# Simple_Lux_Logger.net
KiCad netlist of a schematic drawn in EAGLE
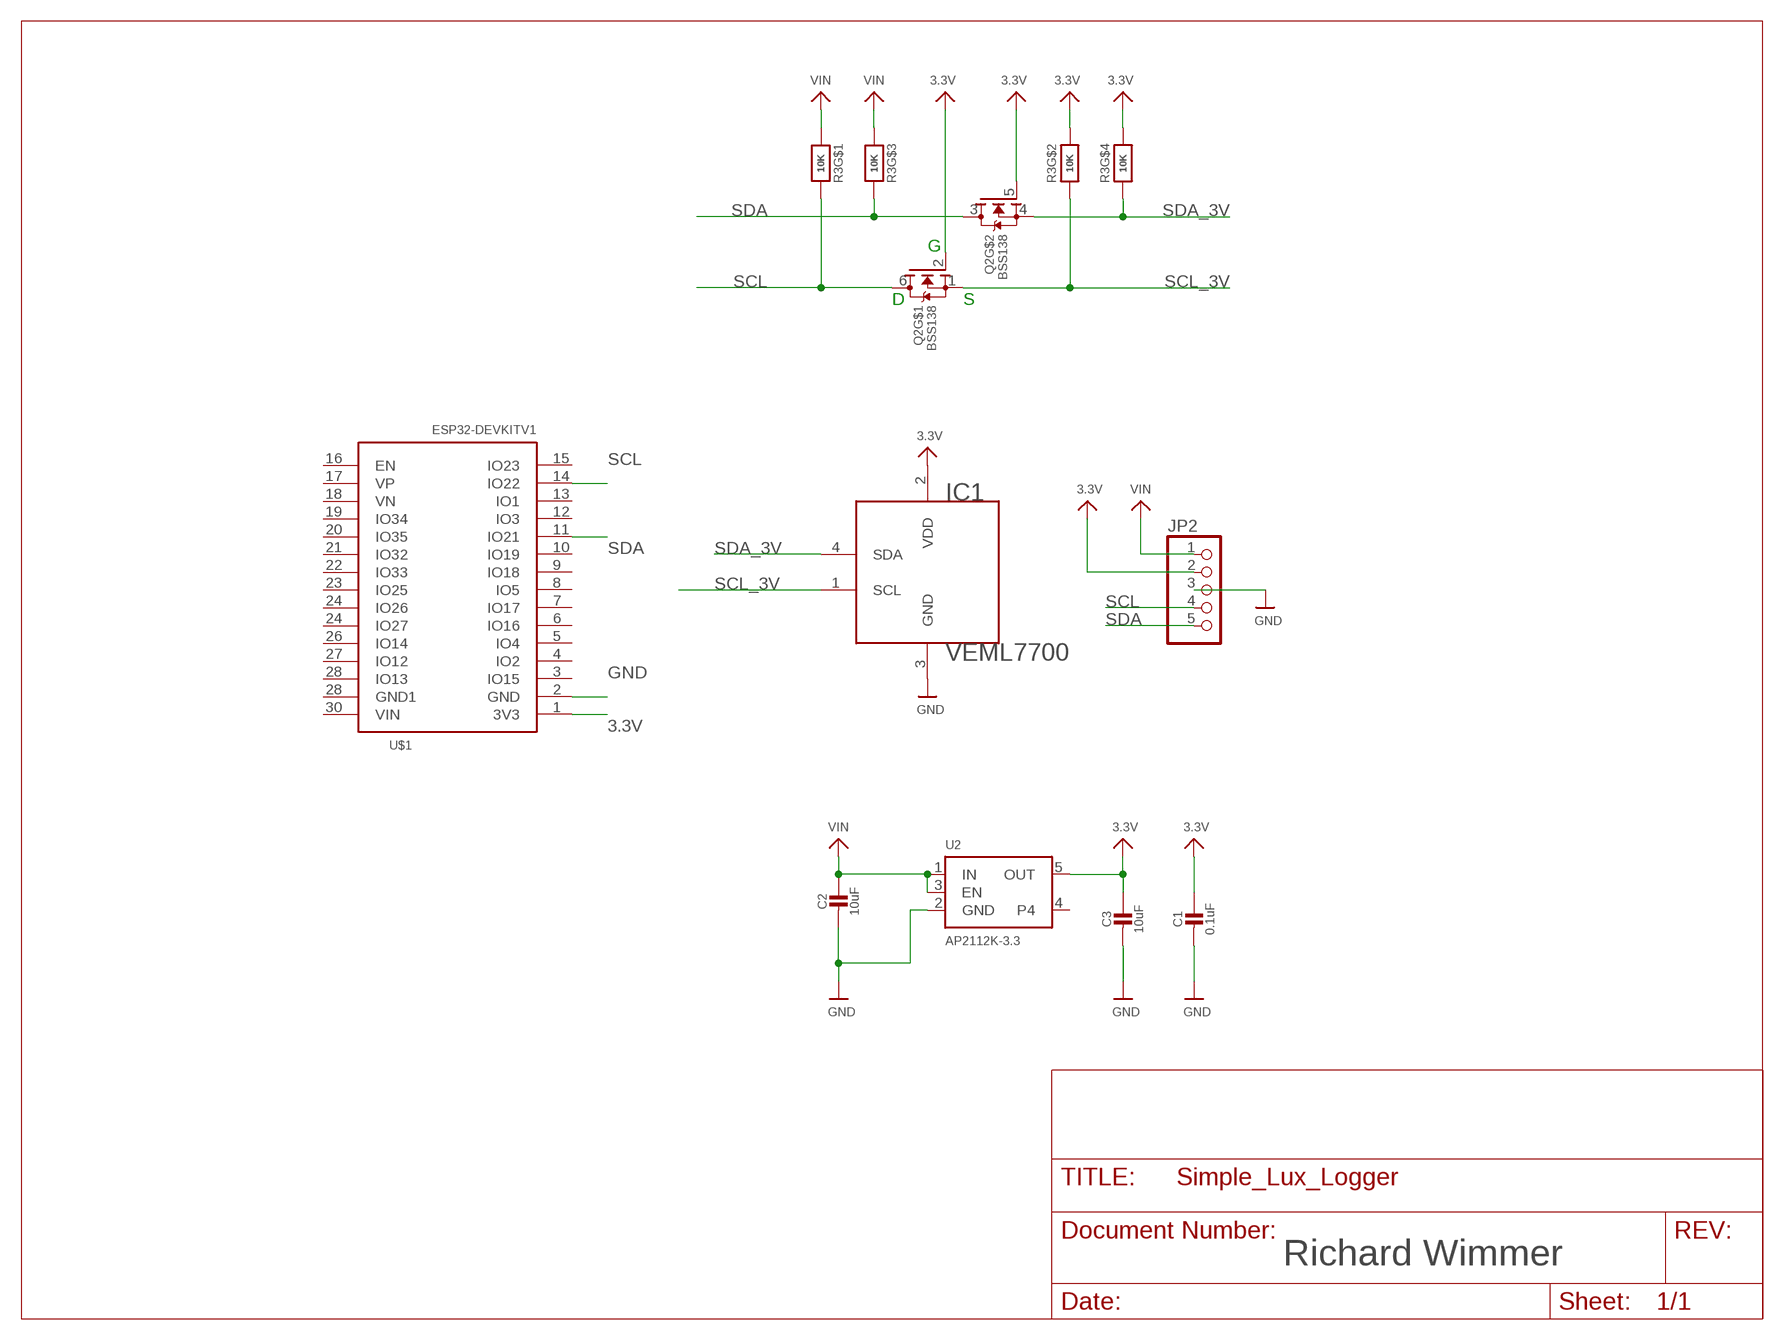
[diagram p0: schematic, sheet 1]

(export (version "E")
  (design (tool "Eeschema 10.0.6"))
  (components
    (comp (ref "C1")
      (value "0.1uF")
      (footprint "eagle-import:0603-NO")
      (libsource (lib "eagle-import") (part "CAP_CERAMIC0603_NO"))
    )
    (comp (ref "C2")
      (value "10uF")
      (footprint "eagle-import:0805-NO")
      (libsource (lib "eagle-import") (part "CAP_CERAMIC0805-NOOUTLINE"))
    )
    (comp (ref "C3")
      (value "10uF")
      (footprint "eagle-import:0805-NO")
      (libsource (lib "eagle-import") (part "CAP_CERAMIC0805-NOOUTLINE"))
    )
    (comp (ref "IC1")
      (value "VEML7700")
      (footprint "eagle-import:VEML7700")
      (libsource (lib "eagle-import") (part "VEML7700"))
    )
    (comp (ref "JP2")
      (value "HEADER-1X5ROUND")
      (footprint "eagle-import:1X05_ROUND")
      (libsource (lib "eagle-import") (part "HEADER-1X5ROUND"))
    )
    (comp (ref "Q2")
      (value "BSS138")
      (footprint "eagle-import:SOT363")
      (libsource (lib "eagle-import") (part "MOSFET-N_DUAL"))
    )
    (comp (ref "R3")
      (value "10K")
      (footprint "eagle-import:RESPACK_4X0603")
      (libsource (lib "eagle-import") (part "RESISTOR_4PACK"))
    )
    (comp (ref "U$1")
      (value "ESP32DEVKITV1")
      (footprint "eagle-import:ESP32-DEVKITV1")
      (libsource (lib "eagle-import") (part "ESP32DEVKITV1"))
    )
    (comp (ref "U2")
      (value "AP2112K-3.3")
      (footprint "eagle-import:SOT23-5")
      (libsource (lib "eagle-import") (part "VREG_SOT23-5"))
    )
  )
  (nets
    (net (code "1") (name "/SCL") (class "Default")
      (node (ref "JP2") (pin "4") (pinfunction "4_4") (pintype "passive"))
      (node (ref "Q2") (pin "6") (pinfunction "D_6") (pintype "bidirectional"))
      (node (ref "R3") (pin "8") (pinfunction "2_8") (pintype "passive"))
      (node (ref "U$1") (pin "14") (pinfunction "IO22_14") (pintype "bidirectional"))
    )
    (net (code "2") (name "/SCL_3V") (class "Default")
      (node (ref "IC1") (pin "1") (pinfunction "SCL_1") (pintype "bidirectional"))
      (node (ref "Q2") (pin "1") (pinfunction "S_1") (pintype "bidirectional"))
      (node (ref "R3") (pin "7") (pinfunction "2_7") (pintype "passive"))
    )
    (net (code "3") (name "/SDA") (class "Default")
      (node (ref "JP2") (pin "5") (pinfunction "5_5") (pintype "passive"))
      (node (ref "Q2") (pin "3") (pinfunction "D_3") (pintype "bidirectional"))
      (node (ref "R3") (pin "6") (pinfunction "2_6") (pintype "passive"))
      (node (ref "U$1") (pin "11") (pinfunction "IO21_11") (pintype "bidirectional"))
    )
    (net (code "4") (name "/SDA_3V") (class "Default")
      (node (ref "IC1") (pin "4") (pinfunction "SDA_4") (pintype "bidirectional"))
      (node (ref "Q2") (pin "4") (pinfunction "S_4") (pintype "bidirectional"))
      (node (ref "R3") (pin "5") (pinfunction "2_5") (pintype "passive"))
    )
    (net (code "5") (name "3.3V") (class "Default")
      (node (ref "C1") (pin "1") (pinfunction "1_1") (pintype "passive"))
      (node (ref "C3") (pin "1") (pinfunction "1_1") (pintype "passive"))
      (node (ref "IC1") (pin "2") (pinfunction "VDD_2") (pintype "power_in"))
      (node (ref "JP2") (pin "2") (pinfunction "2_2") (pintype "passive"))
      (node (ref "Q2") (pin "2") (pinfunction "G_2") (pintype "bidirectional"))
      (node (ref "Q2") (pin "5") (pinfunction "G_5") (pintype "bidirectional"))
      (node (ref "R3") (pin "2") (pinfunction "1_2") (pintype "passive"))
      (node (ref "R3") (pin "4") (pinfunction "1_4") (pintype "passive"))
      (node (ref "U$1") (pin "1") (pinfunction "3V3_1") (pintype "bidirectional"))
      (node (ref "U2") (pin "5") (pinfunction "OUT_5") (pintype "power_in"))
    )
    (net (code "6") (name "GND") (class "Default")
      (node (ref "C1") (pin "2") (pinfunction "2_2") (pintype "passive"))
      (node (ref "C2") (pin "2") (pinfunction "2_2") (pintype "passive"))
      (node (ref "C3") (pin "2") (pinfunction "2_2") (pintype "passive"))
      (node (ref "IC1") (pin "3") (pinfunction "GND_3") (pintype "power_in"))
      (node (ref "JP2") (pin "3") (pinfunction "3_3") (pintype "passive"))
      (node (ref "U$1") (pin "2") (pinfunction "GND_2") (pintype "bidirectional"))
      (node (ref "U2") (pin "2") (pinfunction "GND_2") (pintype "power_in"))
    )
    (net (code "7") (name "VIN") (class "Default")
      (node (ref "C2") (pin "1") (pinfunction "1_1") (pintype "passive"))
      (node (ref "JP2") (pin "1") (pinfunction "1_1") (pintype "passive"))
      (node (ref "R3") (pin "1") (pinfunction "1_1") (pintype "passive"))
      (node (ref "R3") (pin "3") (pinfunction "1_3") (pintype "passive"))
      (node (ref "U2") (pin "1") (pinfunction "IN_1") (pintype "power_in"))
      (node (ref "U2") (pin "3") (pinfunction "EN_3") (pintype "input"))
    )
    (net (code "8") (name "unconnected-(U$1-EN-Pad16)") (class "Default")
      (node (ref "U$1") (pin "16") (pinfunction "EN_16") (pintype "bidirectional"))
    )
    (net (code "9") (name "unconnected-(U$1-GND1-Pad28)") (class "Default")
      (node (ref "U$1") (pin "28") (pinfunction "GND1_28") (pintype "bidirectional"))
    )
    (net (code "10") (name "unconnected-(U$1-IO1-Pad13)") (class "Default")
      (node (ref "U$1") (pin "13") (pinfunction "IO1_13") (pintype "bidirectional"))
    )
    (net (code "11") (name "unconnected-(U$1-IO2-Pad4)") (class "Default")
      (node (ref "U$1") (pin "4") (pinfunction "IO2_4") (pintype "bidirectional"))
    )
    (net (code "12") (name "unconnected-(U$1-IO3-Pad12)") (class "Default")
      (node (ref "U$1") (pin "12") (pinfunction "IO3_12") (pintype "bidirectional"))
    )
    (net (code "13") (name "unconnected-(U$1-IO4-Pad5)") (class "Default")
      (node (ref "U$1") (pin "5") (pinfunction "IO4_5") (pintype "bidirectional"))
    )
    (net (code "14") (name "unconnected-(U$1-IO5-Pad8)") (class "Default")
      (node (ref "U$1") (pin "8") (pinfunction "IO5_8") (pintype "bidirectional"))
    )
    (net (code "15") (name "unconnected-(U$1-IO12-Pad27)") (class "Default")
      (node (ref "U$1") (pin "27") (pinfunction "IO12_27") (pintype "bidirectional"))
    )
    (net (code "16") (name "unconnected-(U$1-IO13-Pad28)") (class "Default")
      (node (ref "U$1") (pin "28") (pinfunction "IO13_28") (pintype "bidirectional"))
    )
    (net (code "17") (name "unconnected-(U$1-IO14-Pad26)") (class "Default")
      (node (ref "U$1") (pin "26") (pinfunction "IO14_26") (pintype "bidirectional"))
    )
    (net (code "18") (name "unconnected-(U$1-IO15-Pad3)") (class "Default")
      (node (ref "U$1") (pin "3") (pinfunction "IO15_3") (pintype "bidirectional"))
    )
    (net (code "19") (name "unconnected-(U$1-IO16-Pad6)") (class "Default")
      (node (ref "U$1") (pin "6") (pinfunction "IO16_6") (pintype "bidirectional"))
    )
    (net (code "20") (name "unconnected-(U$1-IO17-Pad7)") (class "Default")
      (node (ref "U$1") (pin "7") (pinfunction "IO17_7") (pintype "bidirectional"))
    )
    (net (code "21") (name "unconnected-(U$1-IO18-Pad9)") (class "Default")
      (node (ref "U$1") (pin "9") (pinfunction "IO18_9") (pintype "bidirectional"))
    )
    (net (code "22") (name "unconnected-(U$1-IO19-Pad10)") (class "Default")
      (node (ref "U$1") (pin "10") (pinfunction "IO19_10") (pintype "bidirectional"))
    )
    (net (code "23") (name "unconnected-(U$1-IO23-Pad15)") (class "Default")
      (node (ref "U$1") (pin "15") (pinfunction "IO23_15") (pintype "bidirectional"))
    )
    (net (code "24") (name "unconnected-(U$1-IO25-Pad23)") (class "Default")
      (node (ref "U$1") (pin "23") (pinfunction "IO25_23") (pintype "bidirectional"))
    )
    (net (code "25") (name "unconnected-(U$1-IO26-Pad24)") (class "Default")
      (node (ref "U$1") (pin "24") (pinfunction "IO26_24") (pintype "bidirectional"))
    )
    (net (code "26") (name "unconnected-(U$1-IO27-Pad24)") (class "Default")
      (node (ref "U$1") (pin "24") (pinfunction "IO27_24") (pintype "bidirectional"))
    )
    (net (code "27") (name "unconnected-(U$1-IO32-Pad21)") (class "Default")
      (node (ref "U$1") (pin "21") (pinfunction "IO32_21") (pintype "bidirectional"))
    )
    (net (code "28") (name "unconnected-(U$1-IO33-Pad22)") (class "Default")
      (node (ref "U$1") (pin "22") (pinfunction "IO33_22") (pintype "bidirectional"))
    )
    (net (code "29") (name "unconnected-(U$1-IO34-Pad19)") (class "Default")
      (node (ref "U$1") (pin "19") (pinfunction "IO34_19") (pintype "bidirectional"))
    )
    (net (code "30") (name "unconnected-(U$1-IO35-Pad20)") (class "Default")
      (node (ref "U$1") (pin "20") (pinfunction "IO35_20") (pintype "bidirectional"))
    )
    (net (code "31") (name "unconnected-(U$1-VIN-Pad30)") (class "Default")
      (node (ref "U$1") (pin "30") (pinfunction "VIN_30") (pintype "bidirectional"))
    )
    (net (code "32") (name "unconnected-(U$1-VN-Pad18)") (class "Default")
      (node (ref "U$1") (pin "18") (pinfunction "VN_18") (pintype "bidirectional"))
    )
    (net (code "33") (name "unconnected-(U$1-VP-Pad17)") (class "Default")
      (node (ref "U$1") (pin "17") (pinfunction "VP_17") (pintype "bidirectional"))
    )
    (net (code "34") (name "unconnected-(U2-P4-Pad4)") (class "Default")
      (node (ref "U2") (pin "4") (pinfunction "P4_4") (pintype "bidirectional"))
    )
  )
)
